# half_bridge.net
KiCad netlist of a schematic drawn in Altium Designer
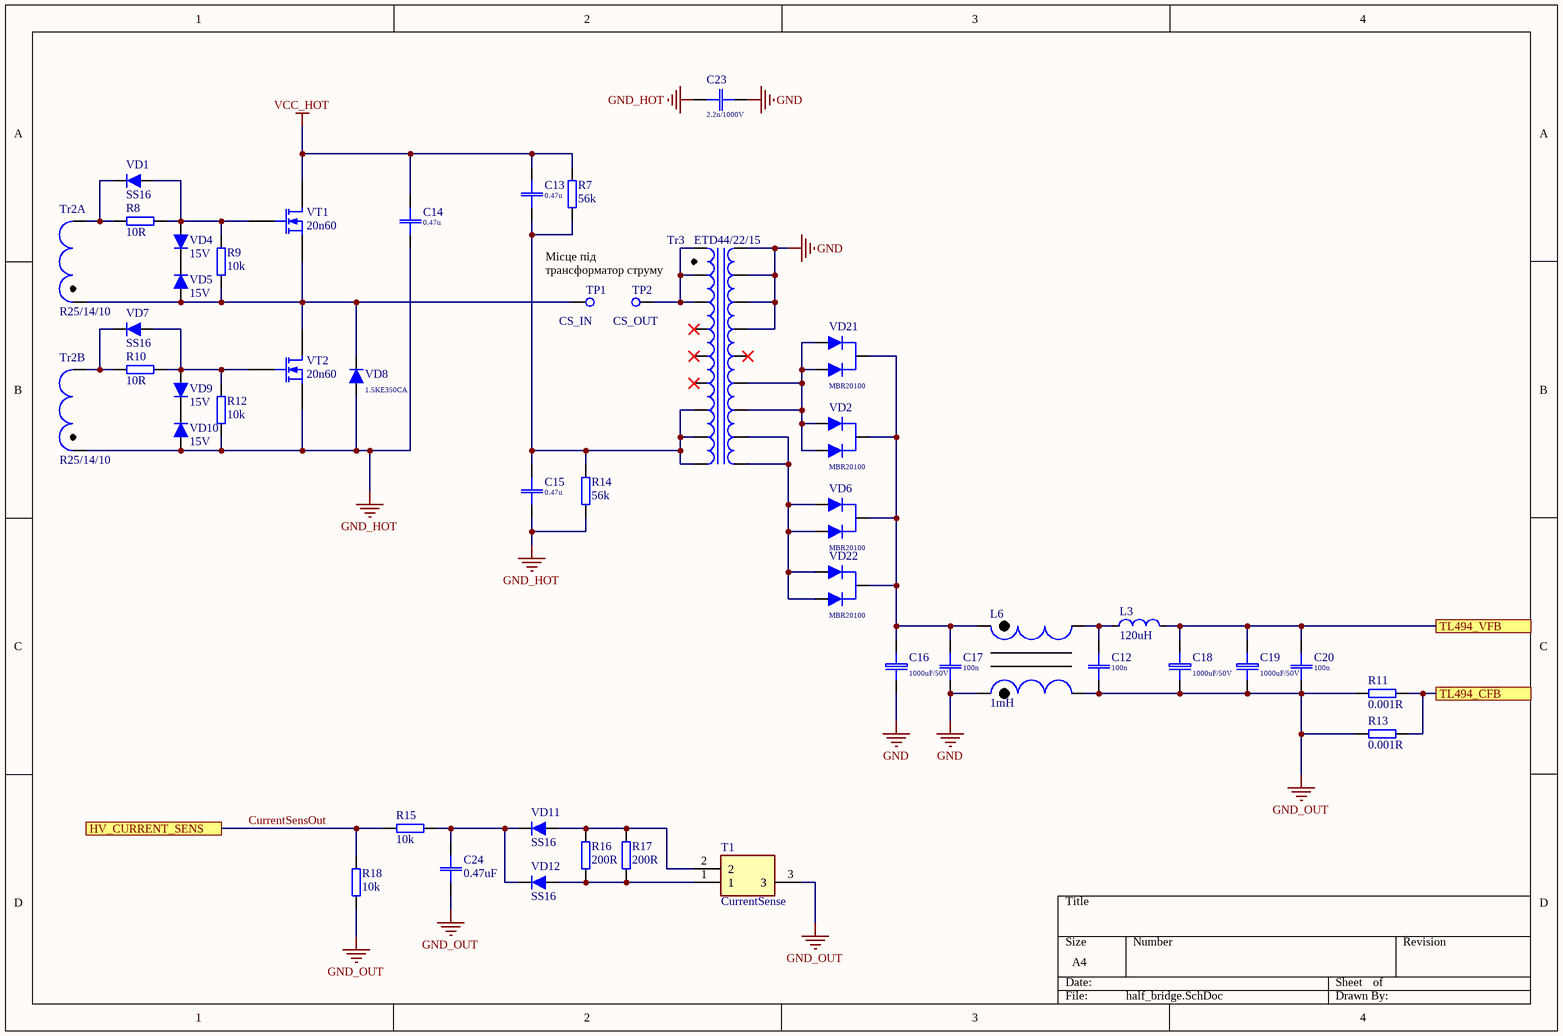
[diagram p0: half_bridge.SchDoc]

(export (version "E")
  (design (tool "Eeschema 10.0.6"))
  (components
    (comp (ref "C12")
      (value "100n")
      (footprint "MKP X2 100nF 275V AC")
      (description "X2 250V AC")
      (libsource (lib "Cap") (part "X2 100n 275V AC"))
    )
    (comp (ref "C13")
      (value "0.47u")
      (footprint "MKP 31.5x11 h21 R27.5")
      (description "MKP10 0.47u 400V AC")
      (libsource (lib "Cap") (part "MKP10 0.47u 400V AC"))
    )
    (comp (ref "C14")
      (value "0.47u")
      (footprint "MKP 31.5x11 h21 R27.5")
      (description "MKP10 0.47u 400V AC")
      (libsource (lib "Cap") (part "MKP10 0.47u 400V AC"))
    )
    (comp (ref "C15")
      (value "0.47u")
      (footprint "MKP 31.5x11 h21 R27.5")
      (description "MKP10 0.47u 400V AC")
      (libsource (lib "Cap") (part "MKP10 0.47u 400V AC"))
    )
    (comp (ref "C16")
      (value "1000uF/50V")
      (footprint "CAP: D16C7.5H25")
      (libsource (lib "PASSIVE") (part "C_EL"))
    )
    (comp (ref "C17")
      (value "100n")
      (footprint "MKP X2 100nF 275V AC")
      (description "X2 250V AC")
      (libsource (lib "Cap") (part "X2 100n 275V AC"))
    )
    (comp (ref "C18")
      (value "1000uF/50V")
      (footprint "CAP: D16C7.5H25")
      (libsource (lib "PASSIVE") (part "C_EL"))
    )
    (comp (ref "C19")
      (value "1000uF/50V")
      (footprint "CAP: D16C7.5H25")
      (libsource (lib "PASSIVE") (part "C_EL"))
    )
    (comp (ref "C20")
      (value "100n")
      (footprint "MKP X2 100nF 275V AC")
      (description "X2 250V AC")
      (libsource (lib "Cap") (part "X2 100n 275V AC"))
    )
    (comp (ref "C23")
      (value "2.2n/1000V")
      (footprint "MKP 26.5x7 h14 R22.5")
      (description "MKP10 0.68u 400V AC")
      (libsource (lib "Cap") (part "MKP10 0.68u 400V AC"))
    )
    (comp (ref "C24") (value "0.47uF") (footprint "CAP: 0603") (libsource (lib "PASSIVE") (part "C_SMD")))
    (comp (ref "L3")
      (value "120uH")
      (footprint "IND: R39.9/24.1/14.5 (H)")
      (libsource (lib "PASSIVE") (part "L_DIP"))
    )
    (comp (ref "L6")
      (value "1mH")
      (footprint "IND: R39.9/24.1/14.5 (H)")
      (libsource (lib "EMI") (part "DROSSEL"))
    )
    (comp (ref "R7") (value "56k") (footprint "RES: 2W H") (libsource (lib "PASSIVE") (part "R_DIP")))
    (comp (ref "R8") (value "10R") (footprint "RES: 0805") (libsource (lib "PASSIVE") (part "R_SMD")))
    (comp (ref "R9") (value "10k") (footprint "RES: 0805") (libsource (lib "PASSIVE") (part "R_SMD")))
    (comp (ref "R10") (value "10R") (footprint "RES: 0805") (libsource (lib "PASSIVE") (part "R_SMD")))
    (comp (ref "R11") (value "0.001R") (footprint "RES: 2512") (libsource (lib "PASSIVE") (part "R_SMD")))
    (comp (ref "R12") (value "10k") (footprint "RES: 0805") (libsource (lib "PASSIVE") (part "R_SMD")))
    (comp (ref "R13") (value "0.001R") (footprint "RES: 2512") (libsource (lib "PASSIVE") (part "R_SMD")))
    (comp (ref "R14") (value "56k") (footprint "RES: 2W H") (libsource (lib "PASSIVE") (part "R_DIP")))
    (comp (ref "R15") (value "10k") (footprint "RES: 0603") (libsource (lib "PASSIVE") (part "R_SMD")))
    (comp (ref "R16") (value "200R") (footprint "RES: 0805") (libsource (lib "PASSIVE") (part "R_SMD")))
    (comp (ref "R17") (value "200R") (footprint "RES: 0805") (libsource (lib "PASSIVE") (part "R_SMD")))
    (comp (ref "R18") (value "10k") (footprint "RES: 0603") (libsource (lib "PASSIVE") (part "R_SMD")))
    (comp (ref "T1")
      (value "CurrentSense")
      (footprint "SamacSys:AC1015")
      (description "Transformer")
      (fields (field (name "MANUFACTURER_PART_NUMBER") "AC-1020"))
      (libsource (lib "*") (part "AC-1020"))
    )
    (comp (ref "TP1")
      (value "CS_IN")
      (footprint "TP: TEST POINT DIP")
      (libsource (lib "OTHER") (part "TEST POINT"))
    )
    (comp (ref "TP2")
      (value "CS_OUT")
      (footprint "TP: TEST POINT DIP")
      (libsource (lib "OTHER") (part "TEST POINT"))
    )
    (comp (ref "Tr2")
      (value "R25/14/10")
      (footprint "IND: R26.9/14.7/11.2 (H)")
      (libsource (lib "GDT_LIB") (part "HulfBribge_Secondary"))
    )
    (comp (ref "Tr3")
      (value "ETD44/22/15")
      (footprint "TRANS: ETD44/22/15")
      (libsource (lib "TRANS") (part "ETD44/22/15"))
    )
    (comp (ref "VD1") (value "SS16") (footprint "DIODE: SMA") (libsource (lib "DIODES") (part "DIODE_SMD")))
    (comp (ref "VD2")
      (value "MBR20100")
      (footprint "DO220D-RB-600")
      (libsource (lib "DIODES") (part "DIODE_DIP_1"))
    )
    (comp (ref "VD4") (value "15V") (footprint "DIODE: SMA") (libsource (lib "DIODES") (part "DIODE_SMD")))
    (comp (ref "VD5") (value "15V") (footprint "DIODE: SMA") (libsource (lib "DIODES") (part "DIODE_SMD")))
    (comp (ref "VD6")
      (value "MBR20100")
      (footprint "DO220D-RB-600")
      (libsource (lib "DIODES") (part "DIODE_DIP_1"))
    )
    (comp (ref "VD7") (value "SS16") (footprint "DIODE: SMA") (libsource (lib "DIODES") (part "DIODE_SMD")))
    (comp (ref "VD8")
      (value "1.5KE350CA")
      (footprint "DO-201-500")
      (libsource (lib "DIODES") (part "DIODE_DIP"))
    )
    (comp (ref "VD9") (value "15V") (footprint "DIODE: SMA") (libsource (lib "DIODES") (part "DIODE_SMD")))
    (comp (ref "VD10") (value "15V") (footprint "DIODE: SMA") (libsource (lib "DIODES") (part "DIODE_SMD")))
    (comp (ref "VD11")
      (value "SS16")
      (footprint "DIODE: SOD123")
      (libsource (lib "DIODES") (part "DIODE_SMD"))
    )
    (comp (ref "VD12")
      (value "SS16")
      (footprint "DIODE: SOD123")
      (libsource (lib "DIODES") (part "DIODE_SMD"))
    )
    (comp (ref "VD21")
      (value "MBR20100")
      (footprint "DO220D-RB-600")
      (libsource (lib "DIODES") (part "DIODE_DIP_1"))
    )
    (comp (ref "VD22")
      (value "MBR20100")
      (footprint "DO220D-RB-600")
      (libsource (lib "DIODES") (part "DIODE_DIP_1"))
    )
    (comp (ref "VT1")
      (value "20n60")
      (footprint "TO247(H)")
      (libsource (lib "TRANSISTOR") (part "MOSFET N_1"))
    )
    (comp (ref "VT2")
      (value "20n60")
      (footprint "TO247(H)")
      (libsource (lib "TRANSISTOR") (part "MOSFET N_1"))
    )
  )
  (nets
    (net (code "1") (name "/CurrentSensOut") (class "Default")
      (node (ref "R15") (pin "2") (pinfunction "2_2") (pintype "passive"))
      (node (ref "R18") (pin "1") (pinfunction "1_1") (pintype "passive"))
    )
    (net (code "2") (name "/TL494_CFB") (class "Default")
      (node (ref "R11") (pin "1") (pinfunction "1_1") (pintype "passive"))
      (node (ref "R13") (pin "1") (pinfunction "1_1") (pintype "passive"))
    )
    (net (code "3") (name "/TL494_VFB") (class "Default")
      (node (ref "C18") (pin "1") (pinfunction "+_1") (pintype "passive"))
      (node (ref "C19") (pin "1") (pinfunction "+_1") (pintype "passive"))
      (node (ref "C20") (pin "1") (pinfunction "1_1") (pintype "passive"))
      (node (ref "L3") (pin "2") (pinfunction "2_2") (pintype "passive"))
    )
    (net (code "4") (name "GND") (class "Default")
      (node (ref "C16") (pin "2") (pinfunction "-_2") (pintype "passive"))
      (node (ref "C17") (pin "2") (pinfunction "2_2") (pintype "passive"))
      (node (ref "C23") (pin "2") (pinfunction "2_2") (pintype "passive"))
      (node (ref "L6") (pin "1") (pinfunction "1_1") (pintype "passive"))
      (node (ref "Tr3") (pin "15") (pinfunction "15_15") (pintype "passive"))
      (node (ref "Tr3") (pin "16") (pinfunction "16_16") (pintype "passive"))
      (node (ref "Tr3") (pin "17") (pinfunction "17_17") (pintype "passive"))
      (node (ref "Tr3") (pin "18") (pinfunction "18_18") (pintype "passive"))
    )
    (net (code "5") (name "GND_HOT") (class "Default")
      (node (ref "C14") (pin "2") (pinfunction "2_2") (pintype "passive"))
      (node (ref "C15") (pin "2") (pinfunction "2_2") (pintype "passive"))
      (node (ref "C23") (pin "1") (pinfunction "1_1") (pintype "passive"))
      (node (ref "R12") (pin "2") (pinfunction "2_2") (pintype "passive"))
      (node (ref "R14") (pin "2") (pinfunction "2_2") (pintype "passive"))
      (node (ref "Tr2") (pin "3") (pinfunction "3_3") (pintype "passive"))
      (node (ref "VD10") (pin "1") (pinfunction "A_1") (pintype "passive"))
      (node (ref "VD8") (pin "1") (pinfunction "A_1") (pintype "passive"))
      (node (ref "VT2") (pin "3") (pinfunction "S_3") (pintype "passive"))
    )
    (net (code "6") (name "GND_OUT") (class "Default")
      (node (ref "C12") (pin "2") (pinfunction "2_2") (pintype "passive"))
      (node (ref "C18") (pin "2") (pinfunction "-_2") (pintype "passive"))
      (node (ref "C19") (pin "2") (pinfunction "-_2") (pintype "passive"))
      (node (ref "C20") (pin "2") (pinfunction "2_2") (pintype "passive"))
      (node (ref "C24") (pin "1") (pinfunction "1_1") (pintype "passive"))
      (node (ref "L6") (pin "2") (pinfunction "2_2") (pintype "passive"))
      (node (ref "R11") (pin "2") (pinfunction "2_2") (pintype "passive"))
      (node (ref "R13") (pin "2") (pinfunction "2_2") (pintype "passive"))
      (node (ref "R18") (pin "2") (pinfunction "2_2") (pintype "passive"))
      (node (ref "T1") (pin "3") (pinfunction "3_3") (pintype "passive"))
    )
    (net (code "7") (name "Net-(C12-Pad1)") (class "Default")
      (node (ref "C12") (pin "1") (pinfunction "1_1") (pintype "passive"))
      (node (ref "L3") (pin "1") (pinfunction "1_1") (pintype "passive"))
      (node (ref "L6") (pin "4") (pinfunction "4_4") (pintype "passive"))
    )
    (net (code "8") (name "Net-(C13-Pad2)") (class "Default")
      (node (ref "C13") (pin "2") (pinfunction "2_2") (pintype "passive"))
      (node (ref "C15") (pin "1") (pinfunction "1_1") (pintype "passive"))
      (node (ref "R14") (pin "1") (pinfunction "1_1") (pintype "passive"))
      (node (ref "R7") (pin "2") (pinfunction "2_2") (pintype "passive"))
      (node (ref "Tr3") (pin "7") (pinfunction "7_7") (pintype "passive"))
      (node (ref "Tr3") (pin "8") (pinfunction "8_8") (pintype "passive"))
      (node (ref "Tr3") (pin "9") (pinfunction "9_9") (pintype "passive"))
    )
    (net (code "9") (name "Net-(C16-+)") (class "Default")
      (node (ref "C16") (pin "1") (pinfunction "+_1") (pintype "passive"))
      (node (ref "C17") (pin "1") (pinfunction "1_1") (pintype "passive"))
      (node (ref "L6") (pin "3") (pinfunction "3_3") (pintype "passive"))
      (node (ref "VD2") (pin "2") (pinfunction "C_2") (pintype "passive"))
      (node (ref "VD21") (pin "2") (pinfunction "C_2") (pintype "passive"))
      (node (ref "VD22") (pin "2") (pinfunction "C_2") (pintype "passive"))
      (node (ref "VD6") (pin "2") (pinfunction "C_2") (pintype "passive"))
    )
    (net (code "10") (name "Net-(TP2-Pad1)") (class "Default")
      (node (ref "TP2") (pin "1") (pintype "passive"))
      (node (ref "Tr3") (pin "1") (pinfunction "1_1") (pintype "passive"))
      (node (ref "Tr3") (pin "2") (pinfunction "2_2") (pintype "passive"))
      (node (ref "Tr3") (pin "3") (pinfunction "3_3") (pintype "passive"))
    )
    (net (code "11") (name "Net-(Tr3-Pad10)") (class "Default")
      (node (ref "Tr3") (pin "10") (pinfunction "10_10") (pintype "passive"))
      (node (ref "Tr3") (pin "11") (pinfunction "11_11") (pintype "passive"))
      (node (ref "VD22") (pin "1") (pinfunction "A_1") (pintype "passive"))
      (node (ref "VD22") (pin "3") (pinfunction "A_3") (pintype "passive"))
      (node (ref "VD6") (pin "1") (pinfunction "A_1") (pintype "passive"))
      (node (ref "VD6") (pin "3") (pinfunction "A_3") (pintype "passive"))
    )
    (net (code "12") (name "Net-(Tr3-Pad12)") (class "Default")
      (node (ref "Tr3") (pin "12") (pinfunction "12_12") (pintype "passive"))
      (node (ref "Tr3") (pin "13") (pinfunction "13_13") (pintype "passive"))
      (node (ref "VD2") (pin "1") (pinfunction "A_1") (pintype "passive"))
      (node (ref "VD2") (pin "3") (pinfunction "A_3") (pintype "passive"))
      (node (ref "VD21") (pin "1") (pinfunction "A_1") (pintype "passive"))
      (node (ref "VD21") (pin "3") (pinfunction "A_3") (pintype "passive"))
    )
    (net (code "13") (name "Net-(VD1-A)") (class "Default")
      (node (ref "R8") (pin "1") (pinfunction "1_1") (pintype "passive"))
      (node (ref "R9") (pin "1") (pinfunction "1_1") (pintype "passive"))
      (node (ref "VD1") (pin "1") (pinfunction "A_1") (pintype "passive"))
      (node (ref "VD4") (pin "1") (pinfunction "A_1") (pintype "passive"))
      (node (ref "VT1") (pin "1") (pinfunction "G_1") (pintype "passive"))
    )
    (net (code "14") (name "Net-(VD1-C)") (class "Default")
      (node (ref "R8") (pin "2") (pinfunction "2_2") (pintype "passive"))
      (node (ref "Tr2") (pin "2") (pinfunction "2_2") (pintype "passive"))
      (node (ref "VD1") (pin "2") (pinfunction "C_2") (pintype "passive"))
    )
    (net (code "15") (name "Net-(VD4-C)") (class "Default")
      (node (ref "VD4") (pin "2") (pinfunction "C_2") (pintype "passive"))
      (node (ref "VD5") (pin "2") (pinfunction "C_2") (pintype "passive"))
    )
    (net (code "16") (name "Net-(VD5-A)") (class "Default")
      (node (ref "R9") (pin "2") (pinfunction "2_2") (pintype "passive"))
      (node (ref "TP1") (pin "1") (pintype "passive"))
      (node (ref "Tr2") (pin "1") (pinfunction "1_1") (pintype "passive"))
      (node (ref "VD5") (pin "1") (pinfunction "A_1") (pintype "passive"))
      (node (ref "VD8") (pin "2") (pinfunction "C_2") (pintype "passive"))
      (node (ref "VT1") (pin "3") (pinfunction "S_3") (pintype "passive"))
      (node (ref "VT2") (pin "2") (pinfunction "D_2") (pintype "passive"))
    )
    (net (code "17") (name "Net-(VD7-A)") (class "Default")
      (node (ref "R10") (pin "1") (pinfunction "1_1") (pintype "passive"))
      (node (ref "R12") (pin "1") (pinfunction "1_1") (pintype "passive"))
      (node (ref "VD7") (pin "1") (pinfunction "A_1") (pintype "passive"))
      (node (ref "VD9") (pin "1") (pinfunction "A_1") (pintype "passive"))
      (node (ref "VT2") (pin "1") (pinfunction "G_1") (pintype "passive"))
    )
    (net (code "18") (name "Net-(VD7-C)") (class "Default")
      (node (ref "R10") (pin "2") (pinfunction "2_2") (pintype "passive"))
      (node (ref "Tr2") (pin "4") (pinfunction "4_4") (pintype "passive"))
      (node (ref "VD7") (pin "2") (pinfunction "C_2") (pintype "passive"))
    )
    (net (code "19") (name "Net-(VD10-C)") (class "Default")
      (node (ref "VD10") (pin "2") (pinfunction "C_2") (pintype "passive"))
      (node (ref "VD9") (pin "2") (pinfunction "C_2") (pintype "passive"))
    )
    (net (code "20") (name "Net-(VD11-A)") (class "Default")
      (node (ref "R16") (pin "1") (pinfunction "1_1") (pintype "passive"))
      (node (ref "R17") (pin "1") (pinfunction "1_1") (pintype "passive"))
      (node (ref "T1") (pin "2") (pinfunction "2_2") (pintype "passive"))
      (node (ref "VD11") (pin "1") (pinfunction "A_1") (pintype "passive"))
    )
    (net (code "21") (name "Net-(VD11-C)") (class "Default")
      (node (ref "C24") (pin "2") (pinfunction "2_2") (pintype "passive"))
      (node (ref "R15") (pin "1") (pinfunction "1_1") (pintype "passive"))
      (node (ref "VD11") (pin "2") (pinfunction "C_2") (pintype "passive"))
      (node (ref "VD12") (pin "2") (pinfunction "C_2") (pintype "passive"))
    )
    (net (code "22") (name "Net-(VD12-A)") (class "Default")
      (node (ref "R16") (pin "2") (pinfunction "2_2") (pintype "passive"))
      (node (ref "R17") (pin "2") (pinfunction "2_2") (pintype "passive"))
      (node (ref "T1") (pin "1") (pinfunction "1_1") (pintype "passive"))
      (node (ref "VD12") (pin "1") (pinfunction "A_1") (pintype "passive"))
    )
    (net (code "23") (name "VCC_HOT") (class "Default")
      (node (ref "C13") (pin "1") (pinfunction "1_1") (pintype "passive"))
      (node (ref "C14") (pin "1") (pinfunction "1_1") (pintype "passive"))
      (node (ref "R7") (pin "1") (pinfunction "1_1") (pintype "passive"))
      (node (ref "VT1") (pin "2") (pinfunction "D_2") (pintype "passive"))
    )
    (net (code "24") (name "unconnected-(Tr3-Pad4)") (class "Default")
      (node (ref "Tr3") (pin "4") (pinfunction "4_4") (pintype "passive+no_connect"))
    )
    (net (code "25") (name "unconnected-(Tr3-Pad5)") (class "Default")
      (node (ref "Tr3") (pin "5") (pinfunction "5_5") (pintype "passive+no_connect"))
    )
    (net (code "26") (name "unconnected-(Tr3-Pad6)") (class "Default")
      (node (ref "Tr3") (pin "6") (pinfunction "6_6") (pintype "passive+no_connect"))
    )
    (net (code "27") (name "unconnected-(Tr3-Pad14)") (class "Default")
      (node (ref "Tr3") (pin "14") (pinfunction "14_14") (pintype "passive+no_connect"))
    )
  )
)
